# Base_Shield_v2.net
KiCad netlist of a schematic drawn in EAGLE
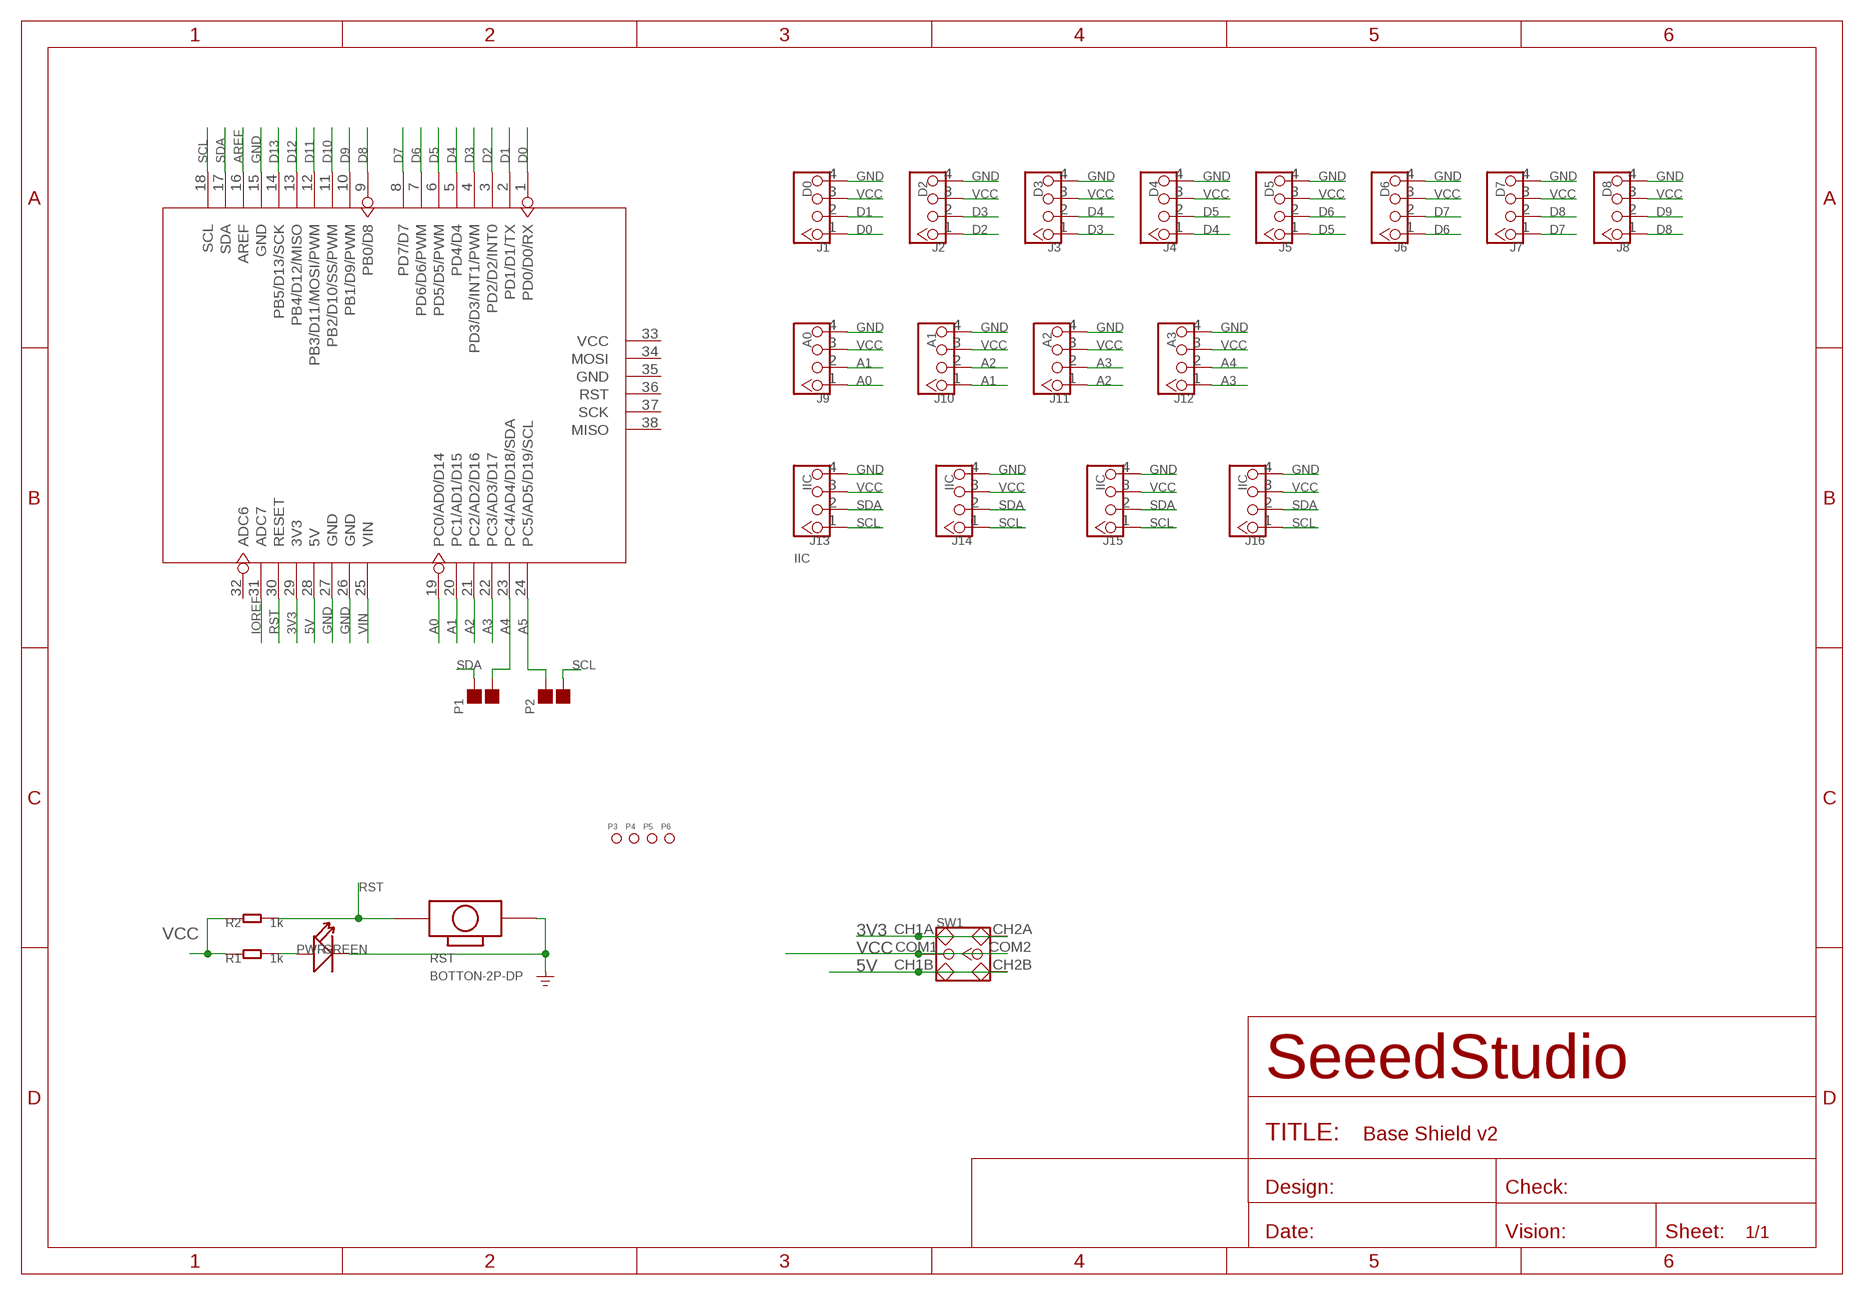
[diagram p0: schematic, sheet 1]

(export (version "E")
  (design (tool "Eeschema 10.0.6"))
  (components
    (comp (ref "J1")
      (value "D0")
      (footprint "eagle-import:4P-2.0")
      (libsource (lib "eagle-import") (part "TWIG-4P-2.0-2.0"))
    )
    (comp (ref "J2")
      (value "D2")
      (footprint "eagle-import:4P-2.0")
      (libsource (lib "eagle-import") (part "TWIG-4P-2.0-2.0"))
    )
    (comp (ref "J3")
      (value "D3")
      (footprint "eagle-import:4P-2.0")
      (libsource (lib "eagle-import") (part "TWIG-4P-2.0-2.0"))
    )
    (comp (ref "J4")
      (value "D4")
      (footprint "eagle-import:4P-2.0")
      (libsource (lib "eagle-import") (part "TWIG-4P-2.0-2.0"))
    )
    (comp (ref "J5")
      (value "D5")
      (footprint "eagle-import:4P-2.0")
      (libsource (lib "eagle-import") (part "TWIG-4P-2.0-2.0"))
    )
    (comp (ref "J6")
      (value "D6")
      (footprint "eagle-import:4P-2.0")
      (libsource (lib "eagle-import") (part "TWIG-4P-2.0-2.0"))
    )
    (comp (ref "J7")
      (value "D7")
      (footprint "eagle-import:4P-2.0")
      (libsource (lib "eagle-import") (part "TWIG-4P-2.0-2.0"))
    )
    (comp (ref "J8")
      (value "D8")
      (footprint "eagle-import:4P-2.0")
      (libsource (lib "eagle-import") (part "TWIG-4P-2.0-2.0"))
    )
    (comp (ref "J9")
      (value "A0")
      (footprint "eagle-import:4P-2.0-90D")
      (libsource (lib "eagle-import") (part "TWIG-4P-2.0'90D'"))
    )
    (comp (ref "J10")
      (value "A1")
      (footprint "eagle-import:4P-2.0-90D")
      (libsource (lib "eagle-import") (part "TWIG-4P-2.0'90D'"))
    )
    (comp (ref "J11")
      (value "A2")
      (footprint "eagle-import:4P-2.0-90D")
      (libsource (lib "eagle-import") (part "TWIG-4P-2.0'90D'"))
    )
    (comp (ref "J12")
      (value "A3")
      (footprint "eagle-import:4P-2.0-90D")
      (libsource (lib "eagle-import") (part "TWIG-4P-2.0'90D'"))
    )
    (comp (ref "J13")
      (value "IIC")
      (footprint "eagle-import:4P-2.0")
      (libsource (lib "eagle-import") (part "TWIG-4P-2.0-2.0"))
    )
    (comp (ref "J14")
      (value "IIC")
      (footprint "eagle-import:4P-2.0")
      (libsource (lib "eagle-import") (part "TWIG-4P-2.0-2.0"))
    )
    (comp (ref "J15")
      (value "IIC")
      (footprint "eagle-import:4P-2.0")
      (libsource (lib "eagle-import") (part "TWIG-4P-2.0-2.0"))
    )
    (comp (ref "J16")
      (value "IIC")
      (footprint "eagle-import:4P-2.0")
      (libsource (lib "eagle-import") (part "TWIG-4P-2.0-2.0"))
    )
    (comp (ref "P1")
      (value "DNP")
      (footprint "eagle-import:2P-SMD-1.78X1.27")
      (libsource (lib "eagle-import") (part "PAD-JUMPER-2P"))
    )
    (comp (ref "P2")
      (value "DNP")
      (footprint "eagle-import:2P-SMD-1.78X1.27")
      (libsource (lib "eagle-import") (part "PAD-JUMPER-2P"))
    )
    (comp (ref "P3")
      (value "PAD-MARK")
      (footprint "eagle-import:ROUND-MARK-1.0")
      (fields (field (name "PARTNO") "DNP"))
      (libsource (lib "eagle-import") (part "PAD-MARK"))
    )
    (comp (ref "P4")
      (value "PAD-MARK")
      (footprint "eagle-import:ROUND-MARK-1.0")
      (fields (field (name "PARTNO") "DNP"))
      (libsource (lib "eagle-import") (part "PAD-MARK"))
    )
    (comp (ref "P5")
      (value "PAD-MARK")
      (footprint "eagle-import:ROUND-MARK-1.0")
      (fields (field (name "PARTNO") "DNP"))
      (libsource (lib "eagle-import") (part "PAD-MARK"))
    )
    (comp (ref "P6")
      (value "PAD-MARK")
      (footprint "eagle-import:ROUND-MARK-1.0")
      (fields (field (name "PARTNO") "DNP"))
      (libsource (lib "eagle-import") (part "PAD-MARK"))
    )
    (comp (ref "PWR")
      (value "GREEN")
      (footprint "eagle-import:LED-2P-2.54-3MM")
      (libsource (lib "eagle-import") (part "LED-3MM"))
    )
    (comp (ref "R1")
      (value "1k")
      (footprint "eagle-import:R0603")
      (libsource (lib "eagle-import") (part "R-0603"))
    )
    (comp (ref "R2")
      (value "1k")
      (footprint "eagle-import:R0603")
      (libsource (lib "eagle-import") (part "R-0603"))
    )
    (comp (ref "RST")
      (value "BOTTON-2P-DP")
      (footprint "eagle-import:2P-7.62X3.56-90D")
      (libsource (lib "eagle-import") (part "BOTTON-2P-90"))
    )
    (comp (ref "SW1")
      (value "SWITCH-2CH-6P'90D'")
      (footprint "eagle-import:6P-2CH-2.5-9.1X3.5X3.2H-90D")
      (libsource (lib "eagle-import") (part "SWITCH-2CH-6P'90D'"))
    )
    (comp (ref "U2")
      (value "DIP Long Blue Female Header")
      (footprint "eagle-import:ARDUINO-38P")
      (libsource (lib "eagle-import") (part "ARDUINO-38P"))
    )
  )
  (nets
    (net (code "1") (name "/3V3") (class "Default")
      (node (ref "SW1") (pin "CH1A") (pinfunction "CH1A_CH1A") (pintype "bidirectional"))
      (node (ref "SW1") (pin "CH2A") (pinfunction "CH2A_CH2A") (pintype "bidirectional"))
      (node (ref "U2") (pin "29") (pinfunction "3V3_29") (pintype "bidirectional"))
    )
    (net (code "2") (name "/5V") (class "Default")
      (node (ref "SW1") (pin "CH1B") (pinfunction "CH1B_CH1B") (pintype "bidirectional"))
      (node (ref "SW1") (pin "CH2B") (pinfunction "CH2B_CH2B") (pintype "bidirectional"))
      (node (ref "U2") (pin "28") (pinfunction "5V_28") (pintype "bidirectional"))
    )
    (net (code "3") (name "/A0") (class "Default")
      (node (ref "J9") (pin "1") (pinfunction "1_1") (pintype "bidirectional"))
      (node (ref "U2") (pin "19") (pinfunction "PC0/AD0/D14_19") (pintype "bidirectional"))
    )
    (net (code "4") (name "/A1") (class "Default")
      (node (ref "J10") (pin "1") (pinfunction "1_1") (pintype "bidirectional"))
      (node (ref "J9") (pin "2") (pinfunction "2_2") (pintype "bidirectional"))
      (node (ref "U2") (pin "20") (pinfunction "PC1/AD1/D15_20") (pintype "bidirectional"))
    )
    (net (code "5") (name "/A2") (class "Default")
      (node (ref "J10") (pin "2") (pinfunction "2_2") (pintype "bidirectional"))
      (node (ref "J11") (pin "1") (pinfunction "1_1") (pintype "bidirectional"))
      (node (ref "U2") (pin "21") (pinfunction "PC2/AD2/D16_21") (pintype "bidirectional"))
    )
    (net (code "6") (name "/A3") (class "Default")
      (node (ref "J11") (pin "2") (pinfunction "2_2") (pintype "bidirectional"))
      (node (ref "J12") (pin "1") (pinfunction "1_1") (pintype "bidirectional"))
      (node (ref "U2") (pin "22") (pinfunction "PC3/AD3/D17_22") (pintype "bidirectional"))
    )
    (net (code "7") (name "/A4") (class "Default")
      (node (ref "J12") (pin "2") (pinfunction "2_2") (pintype "bidirectional"))
      (node (ref "P1") (pin "1") (pinfunction "1_1") (pintype "bidirectional"))
      (node (ref "U2") (pin "23") (pinfunction "PC4/AD4/D18/SDA_23") (pintype "bidirectional"))
    )
    (net (code "8") (name "/A5") (class "Default")
      (node (ref "P2") (pin "2") (pinfunction "2_2") (pintype "bidirectional"))
      (node (ref "U2") (pin "24") (pinfunction "PC5/AD5/D19/SCL_24") (pintype "bidirectional"))
    )
    (net (code "9") (name "/AREF") (class "Default")
      (node (ref "U2") (pin "16") (pinfunction "AREF_16") (pintype "bidirectional"))
    )
    (net (code "10") (name "/D0") (class "Default")
      (node (ref "J1") (pin "1") (pinfunction "1_1") (pintype "bidirectional"))
      (node (ref "U2") (pin "1") (pinfunction "PD0/D0/RX_1") (pintype "bidirectional"))
    )
    (net (code "11") (name "/D1") (class "Default")
      (node (ref "J1") (pin "2") (pinfunction "2_2") (pintype "bidirectional"))
      (node (ref "U2") (pin "2") (pinfunction "PD1/D1/TX_2") (pintype "bidirectional"))
    )
    (net (code "12") (name "/D2") (class "Default")
      (node (ref "J2") (pin "1") (pinfunction "1_1") (pintype "bidirectional"))
      (node (ref "U2") (pin "3") (pinfunction "PD2/D2/INT0_3") (pintype "bidirectional"))
    )
    (net (code "13") (name "/D3") (class "Default")
      (node (ref "J2") (pin "2") (pinfunction "2_2") (pintype "bidirectional"))
      (node (ref "J3") (pin "1") (pinfunction "1_1") (pintype "bidirectional"))
      (node (ref "U2") (pin "4") (pinfunction "PD3/D3/INT1/PWM_4") (pintype "bidirectional"))
    )
    (net (code "14") (name "/D4") (class "Default")
      (node (ref "J3") (pin "2") (pinfunction "2_2") (pintype "bidirectional"))
      (node (ref "J4") (pin "1") (pinfunction "1_1") (pintype "bidirectional"))
      (node (ref "U2") (pin "5") (pinfunction "PD4/D4_5") (pintype "bidirectional"))
    )
    (net (code "15") (name "/D5") (class "Default")
      (node (ref "J4") (pin "2") (pinfunction "2_2") (pintype "bidirectional"))
      (node (ref "J5") (pin "1") (pinfunction "1_1") (pintype "bidirectional"))
      (node (ref "U2") (pin "6") (pinfunction "PD5/D5/PWM_6") (pintype "bidirectional"))
    )
    (net (code "16") (name "/D6") (class "Default")
      (node (ref "J5") (pin "2") (pinfunction "2_2") (pintype "bidirectional"))
      (node (ref "J6") (pin "1") (pinfunction "1_1") (pintype "bidirectional"))
      (node (ref "U2") (pin "7") (pinfunction "PD6/D6/PWM_7") (pintype "bidirectional"))
    )
    (net (code "17") (name "/D7") (class "Default")
      (node (ref "J6") (pin "2") (pinfunction "2_2") (pintype "bidirectional"))
      (node (ref "J7") (pin "1") (pinfunction "1_1") (pintype "bidirectional"))
      (node (ref "U2") (pin "8") (pinfunction "PD7/D7_8") (pintype "bidirectional"))
    )
    (net (code "18") (name "/D8") (class "Default")
      (node (ref "J7") (pin "2") (pinfunction "2_2") (pintype "bidirectional"))
      (node (ref "J8") (pin "1") (pinfunction "1_1") (pintype "bidirectional"))
      (node (ref "U2") (pin "9") (pinfunction "PB0/D8_9") (pintype "bidirectional"))
    )
    (net (code "19") (name "/D9") (class "Default")
      (node (ref "J8") (pin "2") (pinfunction "2_2") (pintype "bidirectional"))
      (node (ref "U2") (pin "10") (pinfunction "PB1/D9/PWM_10") (pintype "bidirectional"))
    )
    (net (code "20") (name "/D10") (class "Default")
      (node (ref "U2") (pin "11") (pinfunction "PB2/D10/SS/PWM_11") (pintype "bidirectional"))
    )
    (net (code "21") (name "/D11") (class "Default")
      (node (ref "U2") (pin "12") (pinfunction "PB3/D11/MOSI/PWM_12") (pintype "bidirectional"))
    )
    (net (code "22") (name "/D12") (class "Default")
      (node (ref "U2") (pin "13") (pinfunction "PB4/D12/MISO_13") (pintype "bidirectional"))
    )
    (net (code "23") (name "/D13") (class "Default")
      (node (ref "U2") (pin "14") (pinfunction "PB5/D13/SCK_14") (pintype "bidirectional"))
    )
    (net (code "24") (name "/IOREF") (class "Default")
      (node (ref "U2") (pin "31") (pinfunction "ADC7_31") (pintype "bidirectional"))
    )
    (net (code "25") (name "/RST") (class "Default")
      (node (ref "R2") (pin "2") (pinfunction "2_2") (pintype "passive"))
      (node (ref "RST") (pin "P$1") (pinfunction "1_P$1") (pintype "bidirectional"))
      (node (ref "U2") (pin "30") (pinfunction "RESET_30") (pintype "bidirectional"))
    )
    (net (code "26") (name "/SCL") (class "Default")
      (node (ref "J13") (pin "1") (pinfunction "1_1") (pintype "bidirectional"))
      (node (ref "J14") (pin "1") (pinfunction "1_1") (pintype "bidirectional"))
      (node (ref "J15") (pin "1") (pinfunction "1_1") (pintype "bidirectional"))
      (node (ref "J16") (pin "1") (pinfunction "1_1") (pintype "bidirectional"))
      (node (ref "P2") (pin "1") (pinfunction "1_1") (pintype "bidirectional"))
      (node (ref "U2") (pin "18") (pinfunction "SCL_18") (pintype "bidirectional"))
    )
    (net (code "27") (name "/SDA") (class "Default")
      (node (ref "J13") (pin "2") (pinfunction "2_2") (pintype "bidirectional"))
      (node (ref "J14") (pin "2") (pinfunction "2_2") (pintype "bidirectional"))
      (node (ref "J15") (pin "2") (pinfunction "2_2") (pintype "bidirectional"))
      (node (ref "J16") (pin "2") (pinfunction "2_2") (pintype "bidirectional"))
      (node (ref "P1") (pin "2") (pinfunction "2_2") (pintype "bidirectional"))
      (node (ref "U2") (pin "17") (pinfunction "SDA_17") (pintype "bidirectional"))
    )
    (net (code "28") (name "/VCC") (class "Default")
      (node (ref "J1") (pin "3") (pinfunction "3_3") (pintype "bidirectional"))
      (node (ref "J10") (pin "3") (pinfunction "3_3") (pintype "bidirectional"))
      (node (ref "J11") (pin "3") (pinfunction "3_3") (pintype "bidirectional"))
      (node (ref "J12") (pin "3") (pinfunction "3_3") (pintype "bidirectional"))
      (node (ref "J13") (pin "3") (pinfunction "3_3") (pintype "bidirectional"))
      (node (ref "J14") (pin "3") (pinfunction "3_3") (pintype "bidirectional"))
      (node (ref "J15") (pin "3") (pinfunction "3_3") (pintype "bidirectional"))
      (node (ref "J16") (pin "3") (pinfunction "3_3") (pintype "bidirectional"))
      (node (ref "J2") (pin "3") (pinfunction "3_3") (pintype "bidirectional"))
      (node (ref "J3") (pin "3") (pinfunction "3_3") (pintype "bidirectional"))
      (node (ref "J4") (pin "3") (pinfunction "3_3") (pintype "bidirectional"))
      (node (ref "J5") (pin "3") (pinfunction "3_3") (pintype "bidirectional"))
      (node (ref "J6") (pin "3") (pinfunction "3_3") (pintype "bidirectional"))
      (node (ref "J7") (pin "3") (pinfunction "3_3") (pintype "bidirectional"))
      (node (ref "J8") (pin "3") (pinfunction "3_3") (pintype "bidirectional"))
      (node (ref "J9") (pin "3") (pinfunction "3_3") (pintype "bidirectional"))
      (node (ref "R1") (pin "1") (pinfunction "1_1") (pintype "passive"))
      (node (ref "R2") (pin "1") (pinfunction "1_1") (pintype "passive"))
      (node (ref "SW1") (pin "COM1") (pinfunction "COM1_COM1") (pintype "bidirectional"))
      (node (ref "SW1") (pin "COM2") (pinfunction "COM2_COM2") (pintype "bidirectional"))
    )
    (net (code "29") (name "/VIN") (class "Default")
      (node (ref "U2") (pin "25") (pinfunction "VIN_25") (pintype "bidirectional"))
    )
    (net (code "30") (name "GND_POWER") (class "Default")
      (node (ref "J1") (pin "4") (pinfunction "4_4") (pintype "bidirectional"))
      (node (ref "J10") (pin "4") (pinfunction "4_4") (pintype "bidirectional"))
      (node (ref "J11") (pin "4") (pinfunction "4_4") (pintype "bidirectional"))
      (node (ref "J12") (pin "4") (pinfunction "4_4") (pintype "bidirectional"))
      (node (ref "J13") (pin "4") (pinfunction "4_4") (pintype "bidirectional"))
      (node (ref "J14") (pin "4") (pinfunction "4_4") (pintype "bidirectional"))
      (node (ref "J15") (pin "4") (pinfunction "4_4") (pintype "bidirectional"))
      (node (ref "J16") (pin "4") (pinfunction "4_4") (pintype "bidirectional"))
      (node (ref "J2") (pin "4") (pinfunction "4_4") (pintype "bidirectional"))
      (node (ref "J3") (pin "4") (pinfunction "4_4") (pintype "bidirectional"))
      (node (ref "J4") (pin "4") (pinfunction "4_4") (pintype "bidirectional"))
      (node (ref "J5") (pin "4") (pinfunction "4_4") (pintype "bidirectional"))
      (node (ref "J6") (pin "4") (pinfunction "4_4") (pintype "bidirectional"))
      (node (ref "J7") (pin "4") (pinfunction "4_4") (pintype "bidirectional"))
      (node (ref "J8") (pin "4") (pinfunction "4_4") (pintype "bidirectional"))
      (node (ref "J9") (pin "4") (pinfunction "4_4") (pintype "bidirectional"))
      (node (ref "PWR") (pin "K") (pinfunction "-_K") (pintype "passive"))
      (node (ref "RST") (pin "P$2") (pinfunction "2_P$2") (pintype "bidirectional"))
      (node (ref "U2") (pin "15") (pinfunction "GND_15") (pintype "bidirectional"))
      (node (ref "U2") (pin "26") (pinfunction "GND_26") (pintype "bidirectional"))
      (node (ref "U2") (pin "27") (pinfunction "GND_27") (pintype "bidirectional"))
    )
    (net (code "31") (name "Net-(PWR-+)") (class "Default")
      (node (ref "PWR") (pin "A") (pinfunction "+_A") (pintype "passive"))
      (node (ref "R1") (pin "2") (pinfunction "2_2") (pintype "passive"))
    )
    (net (code "32") (name "unconnected-(U2-ADC6-Pad32)") (class "Default")
      (node (ref "U2") (pin "32") (pinfunction "ADC6_32") (pintype "bidirectional"))
    )
    (net (code "33") (name "unconnected-(U2-GND-Pad35)") (class "Default")
      (node (ref "U2") (pin "35") (pinfunction "GND_35") (pintype "bidirectional"))
    )
    (net (code "34") (name "unconnected-(U2-MISO-Pad38)") (class "Default")
      (node (ref "U2") (pin "38") (pinfunction "MISO_38") (pintype "bidirectional"))
    )
    (net (code "35") (name "unconnected-(U2-MOSI-Pad34)") (class "Default")
      (node (ref "U2") (pin "34") (pinfunction "MOSI_34") (pintype "bidirectional"))
    )
    (net (code "36") (name "unconnected-(U2-RST-Pad36)") (class "Default")
      (node (ref "U2") (pin "36") (pinfunction "RST_36") (pintype "bidirectional"))
    )
    (net (code "37") (name "unconnected-(U2-SCK-Pad37)") (class "Default")
      (node (ref "U2") (pin "37") (pinfunction "SCK_37") (pintype "bidirectional"))
    )
    (net (code "38") (name "unconnected-(U2-VCC-Pad33)") (class "Default")
      (node (ref "U2") (pin "33") (pinfunction "VCC_33") (pintype "bidirectional"))
    )
  )
)
